# bt-shield-schmitt-totred.net
KiCad netlist of a schematic drawn in EAGLE
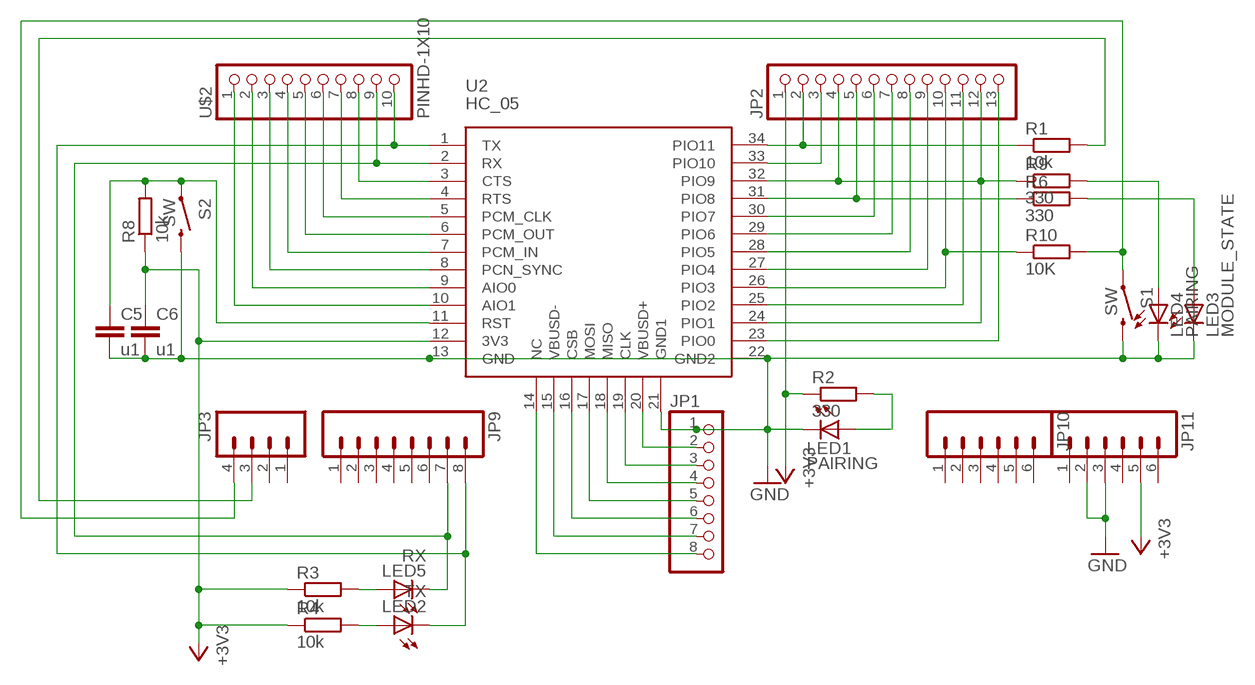
[diagram p0: schematic, sheet 1]

(export (version "E")
  (design (tool "Eeschema 10.0.6"))
  (components
    (comp (ref "C5")
      (value "u1")
      (footprint "eagle-import:C025-025X050")
      (libsource (lib "eagle-import") (part "C-EU025-025X050"))
    )
    (comp (ref "C6")
      (value "u1")
      (footprint "eagle-import:C025-025X050")
      (libsource (lib "eagle-import") (part "C-EU025-025X050"))
    )
    (comp (ref "JP1")
      (value "PINHD-1X8BIG")
      (footprint "eagle-import:1X08-BIG")
      (libsource (lib "eagle-import") (part "PINHD-1X8BIG"))
    )
    (comp (ref "JP2")
      (value "PINHD-1X13_BIG")
      (footprint "eagle-import:1X13-BIG")
      (libsource (lib "eagle-import") (part "PINHD-1X13_BIG"))
    )
    (comp (ref "JP3")
      (value "M04POLAR")
      (footprint "eagle-import:MOLEX-1X4")
      (libsource (lib "eagle-import") (part "M04POLAR"))
    )
    (comp (ref "JP9")
      (value "M081X08")
      (footprint "eagle-import:1X08")
      (libsource (lib "eagle-import") (part "M081X08"))
    )
    (comp (ref "JP10")
      (value "M06SIP")
      (footprint "eagle-import:1X06")
      (libsource (lib "eagle-import") (part "M06SIP"))
    )
    (comp (ref "JP11")
      (value "M06SIP")
      (footprint "eagle-import:1X06")
      (libsource (lib "eagle-import") (part "M06SIP"))
    )
    (comp (ref "LED1")
      (value "PAIRING")
      (footprint "eagle-import:LED5MM")
      (libsource (lib "eagle-import") (part "LED5MM"))
    )
    (comp (ref "LED2")
      (value "TX")
      (footprint "eagle-import:LED2X5")
      (libsource (lib "eagle-import") (part "LEDSQR2X5"))
    )
    (comp (ref "LED3")
      (value "MODULE_STATE")
      (footprint "eagle-import:LED5MM")
      (libsource (lib "eagle-import") (part "LED5MM"))
    )
    (comp (ref "LED4")
      (value "PAIRING")
      (footprint "eagle-import:LED5MM")
      (libsource (lib "eagle-import") (part "LED5MM"))
    )
    (comp (ref "LED5")
      (value "RX")
      (footprint "eagle-import:LED2X5")
      (libsource (lib "eagle-import") (part "LEDSQR2X5"))
    )
    (comp (ref "R1")
      (value "10k")
      (footprint "eagle-import:0207_2V")
      (libsource (lib "eagle-import") (part "R-EU_0207/2V"))
    )
    (comp (ref "R2")
      (value "330")
      (footprint "eagle-import:0204_5")
      (libsource (lib "eagle-import") (part "R-EU_0204/5"))
    )
    (comp (ref "R3")
      (value "10k")
      (footprint "eagle-import:0207_2V")
      (libsource (lib "eagle-import") (part "R-EU_0207/2V"))
    )
    (comp (ref "R4")
      (value "10k")
      (footprint "eagle-import:0207_2V")
      (libsource (lib "eagle-import") (part "R-EU_0207/2V"))
    )
    (comp (ref "R6")
      (value "330")
      (footprint "eagle-import:0204_5")
      (libsource (lib "eagle-import") (part "R-EU_0204/5"))
    )
    (comp (ref "R8")
      (value "10k")
      (footprint "eagle-import:0207_2V")
      (libsource (lib "eagle-import") (part "R-EU_0207/2V"))
    )
    (comp (ref "R9")
      (value "330")
      (footprint "eagle-import:0204_5")
      (libsource (lib "eagle-import") (part "R-EU_0204/5"))
    )
    (comp (ref "R10")
      (value "10K")
      (footprint "eagle-import:0204_7")
      (libsource (lib "eagle-import") (part "R-EU_0204/7"))
    )
    (comp (ref "S1")
      (value "SW")
      (footprint "eagle-import:TACTILE-PTH")
      (libsource (lib "eagle-import") (part "SWITCH-MOMENTARY-2PTH"))
    )
    (comp (ref "S2")
      (value "SW")
      (footprint "eagle-import:TACTILE-PTH")
      (libsource (lib "eagle-import") (part "SWITCH-MOMENTARY-2PTH"))
    )
    (comp (ref "U$2")
      (value "PINHD-1X10")
      (footprint "eagle-import:1X10-BIG")
      (libsource (lib "eagle-import") (part "PINHD-1X10"))
    )
    (comp (ref "U2")
      (value "HC_05")
      (footprint "eagle-import:BLUETOOTH_SMD")
      (libsource (lib "eagle-import") (part "HC_05"))
    )
  )
  (nets
    (net (code "1") (name "+3V3") (class "Default")
      (node (ref "C6") (pin "1") (pinfunction "1_1") (pintype "passive"))
      (node (ref "JP11") (pin "5") (pinfunction "5_5") (pintype "passive"))
      (node (ref "JP2") (pin "1") (pinfunction "1_1") (pintype "passive"))
      (node (ref "R2") (pin "1") (pinfunction "1_1") (pintype "passive"))
      (node (ref "R3") (pin "1") (pinfunction "1_1") (pintype "passive"))
      (node (ref "R4") (pin "1") (pinfunction "1_1") (pintype "passive"))
      (node (ref "R8") (pin "1") (pinfunction "1_1") (pintype "passive"))
      (node (ref "U2") (pin "12") (pinfunction "3V3_12") (pintype "bidirectional"))
    )
    (net (code "2") (name "GND") (class "Default")
      (node (ref "C5") (pin "2") (pinfunction "2_2") (pintype "passive"))
      (node (ref "C6") (pin "2") (pinfunction "2_2") (pintype "passive"))
      (node (ref "JP1") (pin "1") (pinfunction "1_1") (pintype "passive"))
      (node (ref "JP11") (pin "2") (pinfunction "2_2") (pintype "passive"))
      (node (ref "JP11") (pin "3") (pinfunction "3_3") (pintype "passive"))
      (node (ref "LED1") (pin "K") (pinfunction "C_K") (pintype "passive"))
      (node (ref "LED3") (pin "K") (pinfunction "C_K") (pintype "passive"))
      (node (ref "LED4") (pin "K") (pinfunction "C_K") (pintype "passive"))
      (node (ref "S1") (pin "3") (pinfunction "2_3") (pintype "passive"))
      (node (ref "S2") (pin "3") (pinfunction "2_3") (pintype "passive"))
      (node (ref "U2") (pin "13") (pinfunction "GND_13") (pintype "bidirectional"))
      (node (ref "U2") (pin "21") (pinfunction "GND1_21") (pintype "bidirectional"))
      (node (ref "U2") (pin "22") (pinfunction "GND2_22") (pintype "bidirectional"))
    )
    (net (code "3") (name "Net-(JP3-Pad3)") (class "Default")
      (node (ref "JP3") (pin "3") (pinfunction "3_3") (pintype "passive"))
      (node (ref "R1") (pin "2") (pinfunction "2_2") (pintype "passive"))
    )
    (net (code "4") (name "Net-(JP3-Pad4)") (class "Default")
      (node (ref "JP3") (pin "4") (pinfunction "4_4") (pintype "passive"))
      (node (ref "R10") (pin "2") (pinfunction "2_2") (pintype "passive"))
      (node (ref "S1") (pin "1") (pinfunction "1_1") (pintype "passive"))
    )
    (net (code "5") (name "Net-(LED1-PadA)") (class "Default")
      (node (ref "LED1") (pin "A") (pinfunction "A_A") (pintype "passive"))
      (node (ref "R2") (pin "2") (pinfunction "2_2") (pintype "passive"))
    )
    (net (code "6") (name "Net-(LED2-C)") (class "Default")
      (node (ref "JP9") (pin "8") (pinfunction "8_8") (pintype "passive"))
      (node (ref "LED2") (pin "K") (pinfunction "C_K") (pintype "passive"))
      (node (ref "U$2") (pin "10") (pinfunction "10_10") (pintype "passive"))
      (node (ref "U2") (pin "1") (pinfunction "TX_1") (pintype "bidirectional"))
    )
    (net (code "7") (name "Net-(LED2-PadA)") (class "Default")
      (node (ref "LED2") (pin "A") (pinfunction "A_A") (pintype "passive"))
      (node (ref "R4") (pin "2") (pinfunction "2_2") (pintype "passive"))
    )
    (net (code "8") (name "Net-(LED3-PadA)") (class "Default")
      (node (ref "LED3") (pin "A") (pinfunction "A_A") (pintype "passive"))
      (node (ref "R6") (pin "2") (pinfunction "2_2") (pintype "passive"))
    )
    (net (code "9") (name "Net-(LED4-PadA)") (class "Default")
      (node (ref "LED4") (pin "A") (pinfunction "A_A") (pintype "passive"))
      (node (ref "R9") (pin "2") (pinfunction "2_2") (pintype "passive"))
    )
    (net (code "10") (name "Net-(LED5-C)") (class "Default")
      (node (ref "JP9") (pin "7") (pinfunction "7_7") (pintype "passive"))
      (node (ref "LED5") (pin "K") (pinfunction "C_K") (pintype "passive"))
      (node (ref "U$2") (pin "9") (pinfunction "9_9") (pintype "passive"))
      (node (ref "U2") (pin "2") (pinfunction "RX_2") (pintype "bidirectional"))
    )
    (net (code "11") (name "Net-(LED5-PadA)") (class "Default")
      (node (ref "LED5") (pin "A") (pinfunction "A_A") (pintype "passive"))
      (node (ref "R3") (pin "2") (pinfunction "2_2") (pintype "passive"))
    )
    (net (code "12") (name "Net-(U2-AIO0)") (class "Default")
      (node (ref "U$2") (pin "2") (pinfunction "2_2") (pintype "passive"))
      (node (ref "U2") (pin "9") (pinfunction "AIO0_9") (pintype "bidirectional"))
    )
    (net (code "13") (name "Net-(U2-AIO1)") (class "Default")
      (node (ref "U$2") (pin "1") (pinfunction "1_1") (pintype "passive"))
      (node (ref "U2") (pin "10") (pinfunction "AIO1_10") (pintype "bidirectional"))
    )
    (net (code "14") (name "Net-(U2-CLK)") (class "Default")
      (node (ref "JP1") (pin "3") (pinfunction "3_3") (pintype "passive"))
      (node (ref "U2") (pin "19") (pinfunction "CLK_19") (pintype "bidirectional"))
    )
    (net (code "15") (name "Net-(U2-CSB)") (class "Default")
      (node (ref "JP1") (pin "6") (pinfunction "6_6") (pintype "passive"))
      (node (ref "U2") (pin "16") (pinfunction "CSB_16") (pintype "bidirectional"))
    )
    (net (code "16") (name "Net-(U2-CTS)") (class "Default")
      (node (ref "U$2") (pin "8") (pinfunction "8_8") (pintype "passive"))
      (node (ref "U2") (pin "3") (pinfunction "CTS_3") (pintype "bidirectional"))
    )
    (net (code "17") (name "Net-(U2-MISO)") (class "Default")
      (node (ref "JP1") (pin "4") (pinfunction "4_4") (pintype "passive"))
      (node (ref "U2") (pin "18") (pinfunction "MISO_18") (pintype "bidirectional"))
    )
    (net (code "18") (name "Net-(U2-MOSI)") (class "Default")
      (node (ref "JP1") (pin "5") (pinfunction "5_5") (pintype "passive"))
      (node (ref "U2") (pin "17") (pinfunction "MOSI_17") (pintype "bidirectional"))
    )
    (net (code "19") (name "Net-(U2-NC)") (class "Default")
      (node (ref "JP1") (pin "8") (pinfunction "8_8") (pintype "passive"))
      (node (ref "U2") (pin "14") (pinfunction "NC_14") (pintype "bidirectional"))
    )
    (net (code "20") (name "Net-(U2-PCM_CLK)") (class "Default")
      (node (ref "U$2") (pin "6") (pinfunction "6_6") (pintype "passive"))
      (node (ref "U2") (pin "5") (pinfunction "PCM_CLK_5") (pintype "bidirectional"))
    )
    (net (code "21") (name "Net-(U2-PCM_IN)") (class "Default")
      (node (ref "U$2") (pin "4") (pinfunction "4_4") (pintype "passive"))
      (node (ref "U2") (pin "7") (pinfunction "PCM_IN_7") (pintype "bidirectional"))
    )
    (net (code "22") (name "Net-(U2-PCM_OUT)") (class "Default")
      (node (ref "U$2") (pin "5") (pinfunction "5_5") (pintype "passive"))
      (node (ref "U2") (pin "6") (pinfunction "PCM_OUT_6") (pintype "bidirectional"))
    )
    (net (code "23") (name "Net-(U2-PCN_SYNC)") (class "Default")
      (node (ref "U$2") (pin "3") (pinfunction "3_3") (pintype "passive"))
      (node (ref "U2") (pin "8") (pinfunction "PCN_SYNC_8") (pintype "bidirectional"))
    )
    (net (code "24") (name "Net-(U2-PIO0)") (class "Default")
      (node (ref "JP2") (pin "13") (pinfunction "13_13") (pintype "passive"))
      (node (ref "U2") (pin "23") (pinfunction "PIO0_23") (pintype "bidirectional"))
    )
    (net (code "25") (name "Net-(U2-PIO1)") (class "Default")
      (node (ref "JP2") (pin "12") (pinfunction "12_12") (pintype "passive"))
      (node (ref "JP2") (pin "4") (pinfunction "4_4") (pintype "passive"))
      (node (ref "R9") (pin "1") (pinfunction "1_1") (pintype "passive"))
      (node (ref "U2") (pin "24") (pinfunction "PIO1_24") (pintype "bidirectional"))
      (node (ref "U2") (pin "32") (pinfunction "PIO9_32") (pintype "bidirectional"))
    )
    (net (code "26") (name "Net-(U2-PIO2)") (class "Default")
      (node (ref "JP2") (pin "11") (pinfunction "11_11") (pintype "passive"))
      (node (ref "U2") (pin "25") (pinfunction "PIO2_25") (pintype "bidirectional"))
    )
    (net (code "27") (name "Net-(U2-PIO3)") (class "Default")
      (node (ref "JP2") (pin "10") (pinfunction "10_10") (pintype "passive"))
      (node (ref "R10") (pin "1") (pinfunction "1_1") (pintype "passive"))
      (node (ref "U2") (pin "26") (pinfunction "PIO3_26") (pintype "bidirectional"))
    )
    (net (code "28") (name "Net-(U2-PIO4)") (class "Default")
      (node (ref "JP2") (pin "9") (pinfunction "9_9") (pintype "passive"))
      (node (ref "U2") (pin "27") (pinfunction "PIO4_27") (pintype "bidirectional"))
    )
    (net (code "29") (name "Net-(U2-PIO5)") (class "Default")
      (node (ref "JP2") (pin "8") (pinfunction "8_8") (pintype "passive"))
      (node (ref "U2") (pin "28") (pinfunction "PIO5_28") (pintype "bidirectional"))
    )
    (net (code "30") (name "Net-(U2-PIO6)") (class "Default")
      (node (ref "JP2") (pin "7") (pinfunction "7_7") (pintype "passive"))
      (node (ref "U2") (pin "29") (pinfunction "PIO6_29") (pintype "bidirectional"))
    )
    (net (code "31") (name "Net-(U2-PIO7)") (class "Default")
      (node (ref "JP2") (pin "6") (pinfunction "6_6") (pintype "passive"))
      (node (ref "U2") (pin "30") (pinfunction "PIO7_30") (pintype "bidirectional"))
    )
    (net (code "32") (name "Net-(U2-PIO8)") (class "Default")
      (node (ref "JP2") (pin "5") (pinfunction "5_5") (pintype "passive"))
      (node (ref "R6") (pin "1") (pinfunction "1_1") (pintype "passive"))
      (node (ref "U2") (pin "31") (pinfunction "PIO8_31") (pintype "bidirectional"))
    )
    (net (code "33") (name "Net-(U2-PIO10)") (class "Default")
      (node (ref "JP2") (pin "3") (pinfunction "3_3") (pintype "passive"))
      (node (ref "U2") (pin "33") (pinfunction "PIO10_33") (pintype "bidirectional"))
    )
    (net (code "34") (name "Net-(U2-PIO11)") (class "Default")
      (node (ref "JP2") (pin "2") (pinfunction "2_2") (pintype "passive"))
      (node (ref "R1") (pin "1") (pinfunction "1_1") (pintype "passive"))
      (node (ref "U2") (pin "34") (pinfunction "PIO11_34") (pintype "bidirectional"))
    )
    (net (code "35") (name "Net-(U2-RST)") (class "Default")
      (node (ref "C5") (pin "1") (pinfunction "1_1") (pintype "passive"))
      (node (ref "R8") (pin "2") (pinfunction "2_2") (pintype "passive"))
      (node (ref "S2") (pin "1") (pinfunction "1_1") (pintype "passive"))
      (node (ref "U2") (pin "11") (pinfunction "RST_11") (pintype "bidirectional"))
    )
    (net (code "36") (name "Net-(U2-RTS)") (class "Default")
      (node (ref "U$2") (pin "7") (pinfunction "7_7") (pintype "passive"))
      (node (ref "U2") (pin "4") (pinfunction "RTS_4") (pintype "bidirectional"))
    )
    (net (code "37") (name "Net-(U2-VBUSD+)") (class "Default")
      (node (ref "JP1") (pin "2") (pinfunction "2_2") (pintype "passive"))
      (node (ref "U2") (pin "20") (pinfunction "VBUSD+_20") (pintype "bidirectional"))
    )
    (net (code "38") (name "Net-(U2-VBUSD-)") (class "Default")
      (node (ref "JP1") (pin "7") (pinfunction "7_7") (pintype "passive"))
      (node (ref "U2") (pin "15") (pinfunction "VBUSD-_15") (pintype "bidirectional"))
    )
    (net (code "39") (name "unconnected-(JP3-Pad1)") (class "Default")
      (node (ref "JP3") (pin "1") (pinfunction "1_1") (pintype "passive"))
    )
    (net (code "40") (name "unconnected-(JP3-Pad2)") (class "Default")
      (node (ref "JP3") (pin "2") (pinfunction "2_2") (pintype "passive"))
    )
    (net (code "41") (name "unconnected-(JP9-Pad1)") (class "Default")
      (node (ref "JP9") (pin "1") (pinfunction "1_1") (pintype "passive"))
    )
    (net (code "42") (name "unconnected-(JP9-Pad2)") (class "Default")
      (node (ref "JP9") (pin "2") (pinfunction "2_2") (pintype "passive"))
    )
    (net (code "43") (name "unconnected-(JP9-Pad3)") (class "Default")
      (node (ref "JP9") (pin "3") (pinfunction "3_3") (pintype "passive"))
    )
    (net (code "44") (name "unconnected-(JP9-Pad4)") (class "Default")
      (node (ref "JP9") (pin "4") (pinfunction "4_4") (pintype "passive"))
    )
    (net (code "45") (name "unconnected-(JP9-Pad5)") (class "Default")
      (node (ref "JP9") (pin "5") (pinfunction "5_5") (pintype "passive"))
    )
    (net (code "46") (name "unconnected-(JP9-Pad6)") (class "Default")
      (node (ref "JP9") (pin "6") (pinfunction "6_6") (pintype "passive"))
    )
    (net (code "47") (name "unconnected-(JP10-Pad1)") (class "Default")
      (node (ref "JP10") (pin "1") (pinfunction "1_1") (pintype "passive"))
    )
    (net (code "48") (name "unconnected-(JP10-Pad2)") (class "Default")
      (node (ref "JP10") (pin "2") (pinfunction "2_2") (pintype "passive"))
    )
    (net (code "49") (name "unconnected-(JP10-Pad3)") (class "Default")
      (node (ref "JP10") (pin "3") (pinfunction "3_3") (pintype "passive"))
    )
    (net (code "50") (name "unconnected-(JP10-Pad4)") (class "Default")
      (node (ref "JP10") (pin "4") (pinfunction "4_4") (pintype "passive"))
    )
    (net (code "51") (name "unconnected-(JP10-Pad5)") (class "Default")
      (node (ref "JP10") (pin "5") (pinfunction "5_5") (pintype "passive"))
    )
    (net (code "52") (name "unconnected-(JP10-Pad6)") (class "Default")
      (node (ref "JP10") (pin "6") (pinfunction "6_6") (pintype "passive"))
    )
    (net (code "53") (name "unconnected-(JP11-Pad1)") (class "Default")
      (node (ref "JP11") (pin "1") (pinfunction "1_1") (pintype "passive"))
    )
    (net (code "54") (name "unconnected-(JP11-Pad4)") (class "Default")
      (node (ref "JP11") (pin "4") (pinfunction "4_4") (pintype "passive"))
    )
    (net (code "55") (name "unconnected-(JP11-Pad6)") (class "Default")
      (node (ref "JP11") (pin "6") (pinfunction "6_6") (pintype "passive"))
    )
  )
)
